# RAMPS_FanSpansion.net
KiCad netlist of a schematic drawn in EAGLE
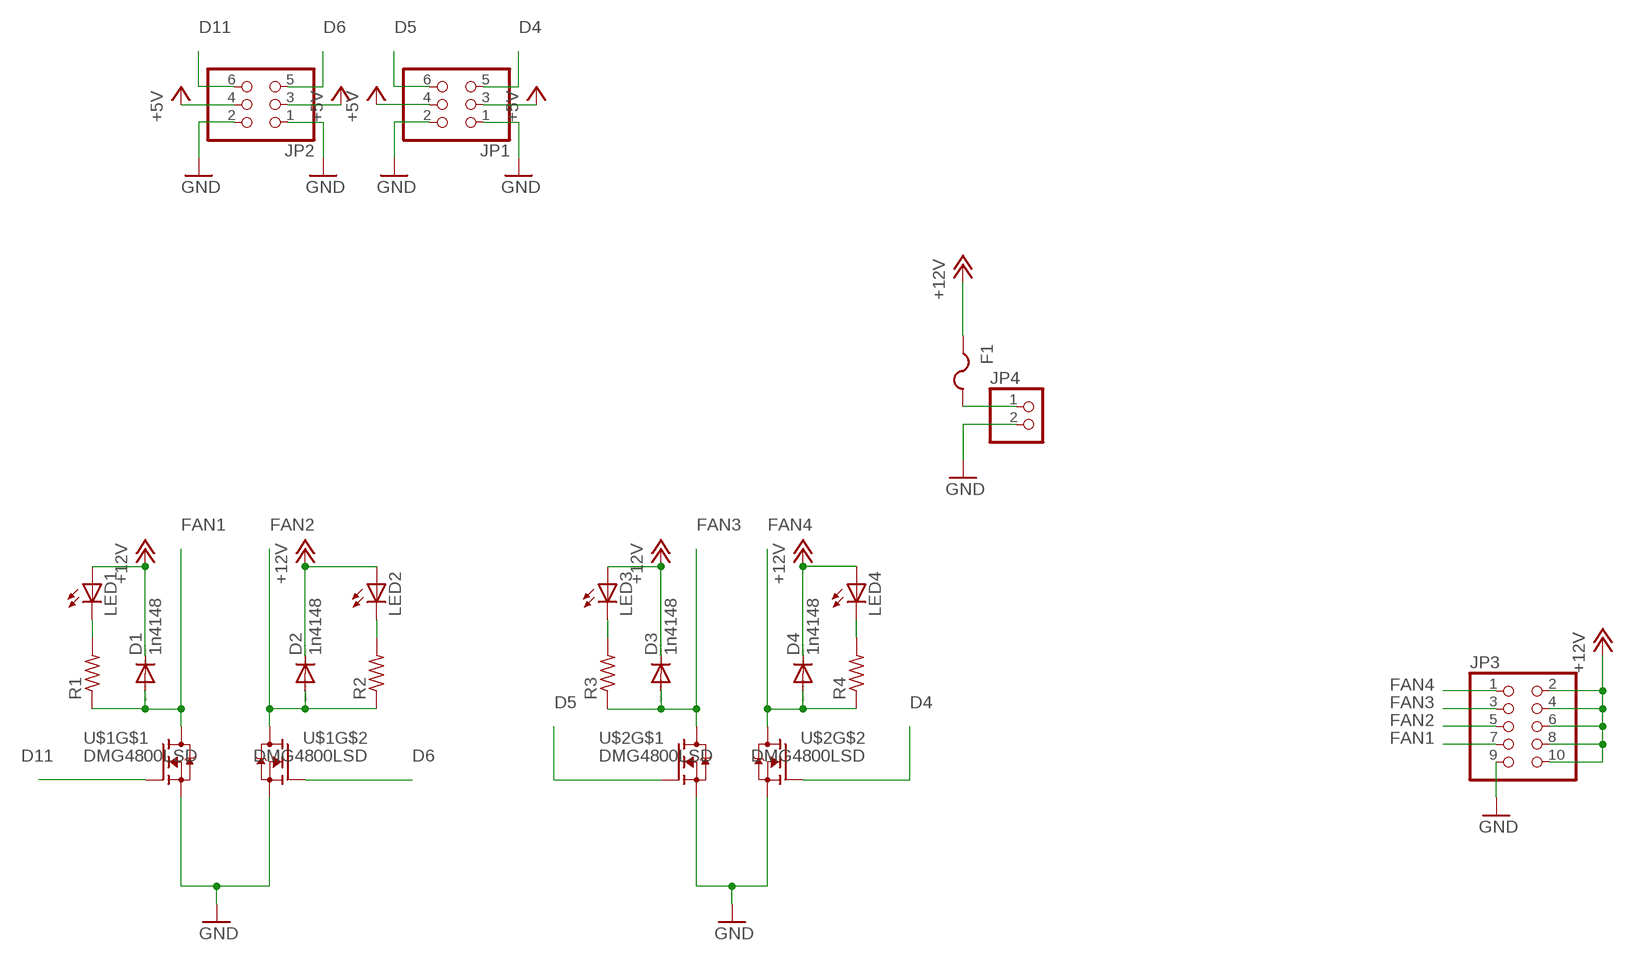
[diagram p0: schematic, sheet 1]

(export (version "E")
  (design (tool "Eeschema 10.0.6"))
  (components
    (comp (ref "D1")
      (value "1n4148")
      (footprint "eagle-import:SOD323-R")
      (libsource (lib "eagle-import") (part "DIODE-SOD323-R"))
    )
    (comp (ref "D2")
      (value "1n4148")
      (footprint "eagle-import:SOD323-R")
      (libsource (lib "eagle-import") (part "DIODE-SOD323-R"))
    )
    (comp (ref "D3")
      (value "1n4148")
      (footprint "eagle-import:SOD323-R")
      (libsource (lib "eagle-import") (part "DIODE-SOD323-R"))
    )
    (comp (ref "D4")
      (value "1n4148")
      (footprint "eagle-import:SOD323-R")
      (libsource (lib "eagle-import") (part "DIODE-SOD323-R"))
    )
    (comp (ref "F1")
      (value "PTCFUSE-1812")
      (footprint "eagle-import:1812")
      (libsource (lib "eagle-import") (part "PTCFUSE-1812"))
    )
    (comp (ref "JP1")
      (value "PINHD-2X3")
      (footprint "eagle-import:2X03")
      (libsource (lib "eagle-import") (part "PINHD-2X3"))
    )
    (comp (ref "JP2")
      (value "PINHD-2X3")
      (footprint "eagle-import:2X03")
      (libsource (lib "eagle-import") (part "PINHD-2X3"))
    )
    (comp (ref "JP3")
      (value "PINHD-2X5")
      (footprint "eagle-import:2X05")
      (libsource (lib "eagle-import") (part "PINHD-2X5"))
    )
    (comp (ref "JP4")
      (value "PINHD-1X2")
      (footprint "eagle-import:1X02")
      (libsource (lib "eagle-import") (part "PINHD-1X2"))
    )
    (comp (ref "LED1")
      (value "LEDSML0805")
      (footprint "eagle-import:SML0805")
      (libsource (lib "eagle-import") (part "LEDSML0805"))
    )
    (comp (ref "LED2")
      (value "LEDSML0805")
      (footprint "eagle-import:SML0805")
      (libsource (lib "eagle-import") (part "LEDSML0805"))
    )
    (comp (ref "LED3")
      (value "LEDSML0805")
      (footprint "eagle-import:SML0805")
      (libsource (lib "eagle-import") (part "LEDSML0805"))
    )
    (comp (ref "LED4")
      (value "LEDSML0805")
      (footprint "eagle-import:SML0805")
      (libsource (lib "eagle-import") (part "LEDSML0805"))
    )
    (comp (ref "R1")
      (value "R-US_R0805")
      (footprint "eagle-import:R0805")
      (libsource (lib "eagle-import") (part "R-US_R0805"))
    )
    (comp (ref "R2")
      (value "R-US_R0805")
      (footprint "eagle-import:R0805")
      (libsource (lib "eagle-import") (part "R-US_R0805"))
    )
    (comp (ref "R3")
      (value "R-US_R0805")
      (footprint "eagle-import:R0805")
      (libsource (lib "eagle-import") (part "R-US_R0805"))
    )
    (comp (ref "R4")
      (value "R-US_R0805")
      (footprint "eagle-import:R0805")
      (libsource (lib "eagle-import") (part "R-US_R0805"))
    )
    (comp (ref "U$1")
      (value "DMG4800LSD")
      (footprint "eagle-import:SO08")
      (libsource (lib "eagle-import") (part "DMG4800LSD"))
    )
    (comp (ref "U$2")
      (value "DMG4800LSD")
      (footprint "eagle-import:SO08")
      (libsource (lib "eagle-import") (part "DMG4800LSD"))
    )
  )
  (nets
    (net (code "1") (name "+5V") (class "Default")
      (node (ref "JP1") (pin "3") (pinfunction "3_3") (pintype "passive"))
      (node (ref "JP1") (pin "4") (pinfunction "4_4") (pintype "passive"))
      (node (ref "JP2") (pin "3") (pinfunction "3_3") (pintype "passive"))
      (node (ref "JP2") (pin "4") (pinfunction "4_4") (pintype "passive"))
    )
    (net (code "2") (name "+12V") (class "Default")
      (node (ref "D1") (pin "C") (pinfunction "C_C") (pintype "passive"))
      (node (ref "D2") (pin "C") (pinfunction "C_C") (pintype "passive"))
      (node (ref "D3") (pin "C") (pinfunction "C_C") (pintype "passive"))
      (node (ref "D4") (pin "C") (pinfunction "C_C") (pintype "passive"))
      (node (ref "F1") (pin "1") (pinfunction "1_1") (pintype "passive"))
      (node (ref "JP3") (pin "10") (pinfunction "10_10") (pintype "passive"))
      (node (ref "JP3") (pin "2") (pinfunction "2_2") (pintype "passive"))
      (node (ref "JP3") (pin "4") (pinfunction "4_4") (pintype "passive"))
      (node (ref "JP3") (pin "6") (pinfunction "6_6") (pintype "passive"))
      (node (ref "JP3") (pin "8") (pinfunction "8_8") (pintype "passive"))
      (node (ref "LED1") (pin "A") (pinfunction "A_A") (pintype "passive"))
      (node (ref "LED2") (pin "A") (pinfunction "A_A") (pintype "passive"))
      (node (ref "LED3") (pin "A") (pinfunction "A_A") (pintype "passive"))
      (node (ref "LED4") (pin "A") (pinfunction "A_A") (pintype "passive"))
    )
    (net (code "3") (name "/D4") (class "Default")
      (node (ref "JP1") (pin "5") (pinfunction "5_5") (pintype "passive"))
      (node (ref "U$2") (pin "4") (pinfunction "G_4") (pintype "passive"))
    )
    (net (code "4") (name "/D5") (class "Default")
      (node (ref "JP1") (pin "6") (pinfunction "6_6") (pintype "passive"))
      (node (ref "U$2") (pin "2") (pinfunction "G_2") (pintype "passive"))
    )
    (net (code "5") (name "/D6") (class "Default")
      (node (ref "JP2") (pin "5") (pinfunction "5_5") (pintype "passive"))
      (node (ref "U$1") (pin "4") (pinfunction "G_4") (pintype "passive"))
    )
    (net (code "6") (name "/D11") (class "Default")
      (node (ref "JP2") (pin "6") (pinfunction "6_6") (pintype "passive"))
      (node (ref "U$1") (pin "2") (pinfunction "G_2") (pintype "passive"))
    )
    (net (code "7") (name "/FAN1") (class "Default")
      (node (ref "D1") (pin "A") (pinfunction "A_A") (pintype "passive"))
      (node (ref "JP3") (pin "7") (pinfunction "7_7") (pintype "passive"))
      (node (ref "R1") (pin "1") (pinfunction "1_1") (pintype "passive"))
      (node (ref "U$1") (pin "7") (pinfunction "D_7") (pintype "passive"))
      (node (ref "U$1") (pin "8") (pinfunction "D_8") (pintype "passive"))
    )
    (net (code "8") (name "/FAN2") (class "Default")
      (node (ref "D2") (pin "A") (pinfunction "A_A") (pintype "passive"))
      (node (ref "JP3") (pin "5") (pinfunction "5_5") (pintype "passive"))
      (node (ref "R2") (pin "1") (pinfunction "1_1") (pintype "passive"))
      (node (ref "U$1") (pin "5") (pinfunction "D_5") (pintype "passive"))
      (node (ref "U$1") (pin "6") (pinfunction "D_6") (pintype "passive"))
    )
    (net (code "9") (name "/FAN3") (class "Default")
      (node (ref "D3") (pin "A") (pinfunction "A_A") (pintype "passive"))
      (node (ref "JP3") (pin "3") (pinfunction "3_3") (pintype "passive"))
      (node (ref "R3") (pin "1") (pinfunction "1_1") (pintype "passive"))
      (node (ref "U$2") (pin "7") (pinfunction "D_7") (pintype "passive"))
      (node (ref "U$2") (pin "8") (pinfunction "D_8") (pintype "passive"))
    )
    (net (code "10") (name "/FAN4") (class "Default")
      (node (ref "D4") (pin "A") (pinfunction "A_A") (pintype "passive"))
      (node (ref "JP3") (pin "1") (pinfunction "1_1") (pintype "passive"))
      (node (ref "R4") (pin "1") (pinfunction "1_1") (pintype "passive"))
      (node (ref "U$2") (pin "5") (pinfunction "D_5") (pintype "passive"))
      (node (ref "U$2") (pin "6") (pinfunction "D_6") (pintype "passive"))
    )
    (net (code "11") (name "GND") (class "Default")
      (node (ref "JP1") (pin "1") (pinfunction "1_1") (pintype "passive"))
      (node (ref "JP1") (pin "2") (pinfunction "2_2") (pintype "passive"))
      (node (ref "JP2") (pin "1") (pinfunction "1_1") (pintype "passive"))
      (node (ref "JP2") (pin "2") (pinfunction "2_2") (pintype "passive"))
      (node (ref "JP3") (pin "9") (pinfunction "9_9") (pintype "passive"))
      (node (ref "JP4") (pin "2") (pinfunction "2_2") (pintype "passive"))
      (node (ref "U$1") (pin "1") (pinfunction "S_1") (pintype "passive"))
      (node (ref "U$1") (pin "3") (pinfunction "S_3") (pintype "passive"))
      (node (ref "U$2") (pin "1") (pinfunction "S_1") (pintype "passive"))
      (node (ref "U$2") (pin "3") (pinfunction "S_3") (pintype "passive"))
    )
    (net (code "12") (name "Net-(F1-Pad2)") (class "Default")
      (node (ref "F1") (pin "2") (pinfunction "2_2") (pintype "passive"))
      (node (ref "JP4") (pin "1") (pinfunction "1_1") (pintype "passive"))
    )
    (net (code "13") (name "Net-(LED1-PadC)") (class "Default")
      (node (ref "LED1") (pin "C") (pinfunction "C_C") (pintype "passive"))
      (node (ref "R1") (pin "2") (pinfunction "2_2") (pintype "passive"))
    )
    (net (code "14") (name "Net-(LED2-PadC)") (class "Default")
      (node (ref "LED2") (pin "C") (pinfunction "C_C") (pintype "passive"))
      (node (ref "R2") (pin "2") (pinfunction "2_2") (pintype "passive"))
    )
    (net (code "15") (name "Net-(LED3-PadC)") (class "Default")
      (node (ref "LED3") (pin "C") (pinfunction "C_C") (pintype "passive"))
      (node (ref "R3") (pin "2") (pinfunction "2_2") (pintype "passive"))
    )
    (net (code "16") (name "Net-(LED4-PadC)") (class "Default")
      (node (ref "LED4") (pin "C") (pinfunction "C_C") (pintype "passive"))
      (node (ref "R4") (pin "2") (pinfunction "2_2") (pintype "passive"))
    )
  )
)
